# DINx2.net
KiCad netlist of a schematic drawn in EAGLE
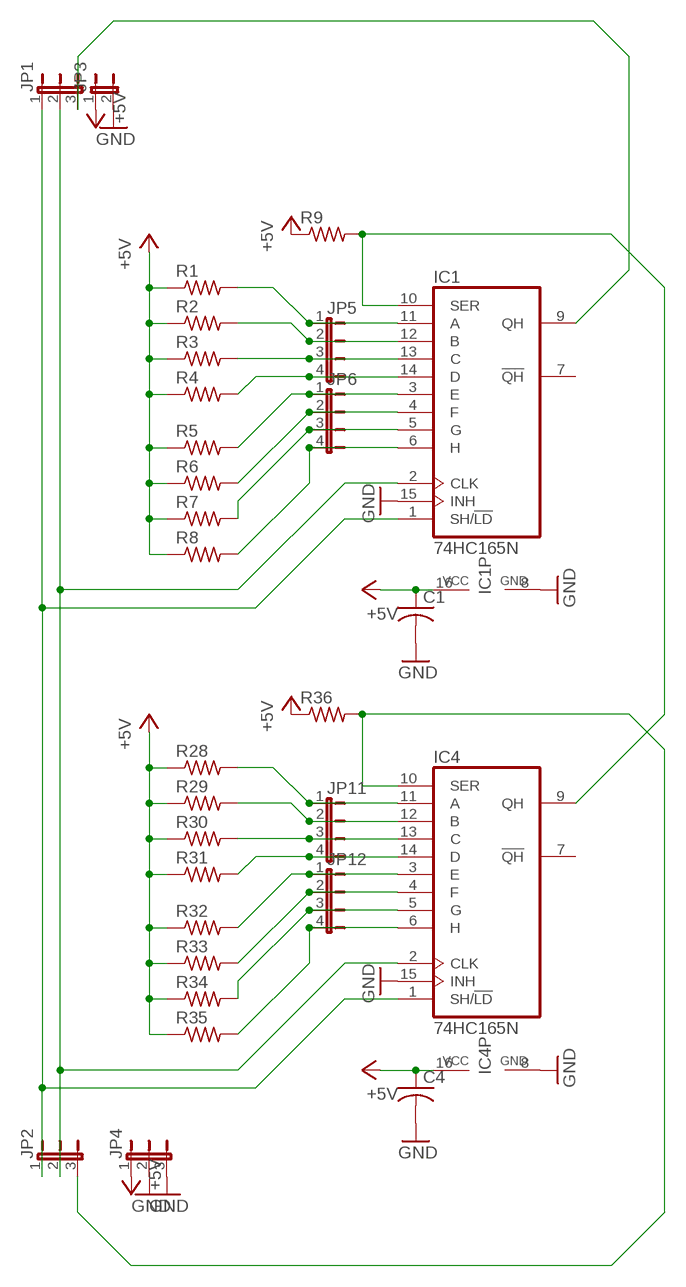
[diagram p0: schematic, sheet 1]

(export (version "E")
  (design (tool "Eeschema 10.0.6"))
  (components
    (comp (ref "C1")
      (value "C-US025-025X050")
      (footprint "eagle-import:C025-025X050")
      (libsource (lib "eagle-import") (part "C-US025-025X050"))
    )
    (comp (ref "C4")
      (value "C-US025-025X050")
      (footprint "eagle-import:C025-025X050")
      (libsource (lib "eagle-import") (part "C-US025-025X050"))
    )
    (comp (ref "IC1")
      (value "74HC165N")
      (footprint "eagle-import:DIL16")
      (libsource (lib "eagle-import") (part "74165NHC"))
    )
    (comp (ref "IC4")
      (value "74HC165N")
      (footprint "eagle-import:DIL16")
      (libsource (lib "eagle-import") (part "74165NHC"))
    )
    (comp (ref "JP1")
      (value "JP2E")
      (footprint "eagle-import:JP2")
      (libsource (lib "eagle-import") (part "JP2E"))
    )
    (comp (ref "JP2")
      (value "JP2E")
      (footprint "eagle-import:JP2")
      (libsource (lib "eagle-import") (part "JP2E"))
    )
    (comp (ref "JP3")
      (value "JP1E")
      (footprint "eagle-import:JP1")
      (libsource (lib "eagle-import") (part "JP1E"))
    )
    (comp (ref "JP4")
      (value "JP2E")
      (footprint "eagle-import:JP2")
      (libsource (lib "eagle-import") (part "JP2E"))
    )
    (comp (ref "JP5")
      (value "JP4E")
      (footprint "eagle-import:JP4")
      (libsource (lib "eagle-import") (part "JP4E"))
    )
    (comp (ref "JP6")
      (value "JP4E")
      (footprint "eagle-import:JP4")
      (libsource (lib "eagle-import") (part "JP4E"))
    )
    (comp (ref "JP11")
      (value "JP4E")
      (footprint "eagle-import:JP4")
      (libsource (lib "eagle-import") (part "JP4E"))
    )
    (comp (ref "JP12")
      (value "JP4E")
      (footprint "eagle-import:JP4")
      (libsource (lib "eagle-import") (part "JP4E"))
    )
    (comp (ref "R1")
      (value "R-US_0207/2V")
      (footprint "eagle-import:0207_2V")
      (libsource (lib "eagle-import") (part "R-US_0207/2V"))
    )
    (comp (ref "R2")
      (value "R-US_0207/2V")
      (footprint "eagle-import:0207_2V")
      (libsource (lib "eagle-import") (part "R-US_0207/2V"))
    )
    (comp (ref "R3")
      (value "R-US_0207/2V")
      (footprint "eagle-import:0207_2V")
      (libsource (lib "eagle-import") (part "R-US_0207/2V"))
    )
    (comp (ref "R4")
      (value "R-US_0207/2V")
      (footprint "eagle-import:0207_2V")
      (libsource (lib "eagle-import") (part "R-US_0207/2V"))
    )
    (comp (ref "R5")
      (value "R-US_0207/2V")
      (footprint "eagle-import:0207_2V")
      (libsource (lib "eagle-import") (part "R-US_0207/2V"))
    )
    (comp (ref "R6")
      (value "R-US_0207/2V")
      (footprint "eagle-import:0207_2V")
      (libsource (lib "eagle-import") (part "R-US_0207/2V"))
    )
    (comp (ref "R7")
      (value "R-US_0207/2V")
      (footprint "eagle-import:0207_2V")
      (libsource (lib "eagle-import") (part "R-US_0207/2V"))
    )
    (comp (ref "R8")
      (value "R-US_0207/2V")
      (footprint "eagle-import:0207_2V")
      (libsource (lib "eagle-import") (part "R-US_0207/2V"))
    )
    (comp (ref "R9")
      (value "R-US_0207/2V")
      (footprint "eagle-import:0207_2V")
      (libsource (lib "eagle-import") (part "R-US_0207/2V"))
    )
    (comp (ref "R28")
      (value "R-US_0207/2V")
      (footprint "eagle-import:0207_2V")
      (libsource (lib "eagle-import") (part "R-US_0207/2V"))
    )
    (comp (ref "R29")
      (value "R-US_0207/2V")
      (footprint "eagle-import:0207_2V")
      (libsource (lib "eagle-import") (part "R-US_0207/2V"))
    )
    (comp (ref "R30")
      (value "R-US_0207/2V")
      (footprint "eagle-import:0207_2V")
      (libsource (lib "eagle-import") (part "R-US_0207/2V"))
    )
    (comp (ref "R31")
      (value "R-US_0207/2V")
      (footprint "eagle-import:0207_2V")
      (libsource (lib "eagle-import") (part "R-US_0207/2V"))
    )
    (comp (ref "R32")
      (value "R-US_0207/2V")
      (footprint "eagle-import:0207_2V")
      (libsource (lib "eagle-import") (part "R-US_0207/2V"))
    )
    (comp (ref "R33")
      (value "R-US_0207/2V")
      (footprint "eagle-import:0207_2V")
      (libsource (lib "eagle-import") (part "R-US_0207/2V"))
    )
    (comp (ref "R34")
      (value "R-US_0207/2V")
      (footprint "eagle-import:0207_2V")
      (libsource (lib "eagle-import") (part "R-US_0207/2V"))
    )
    (comp (ref "R35")
      (value "R-US_0207/2V")
      (footprint "eagle-import:0207_2V")
      (libsource (lib "eagle-import") (part "R-US_0207/2V"))
    )
    (comp (ref "R36")
      (value "R-US_0207/2V")
      (footprint "eagle-import:0207_2V")
      (libsource (lib "eagle-import") (part "R-US_0207/2V"))
    )
  )
  (nets
    (net (code "1") (name "+5V") (class "Default")
      (node (ref "C1") (pin "1") (pinfunction "1_1") (pintype "passive"))
      (node (ref "C4") (pin "1") (pinfunction "1_1") (pintype "passive"))
      (node (ref "IC1") (pin "16") (pinfunction "VCC_16") (pintype "power_in"))
      (node (ref "IC4") (pin "16") (pinfunction "VCC_16") (pintype "power_in"))
      (node (ref "JP3") (pin "1") (pinfunction "1_1") (pintype "passive"))
      (node (ref "JP4") (pin "1") (pinfunction "1_1") (pintype "passive"))
      (node (ref "R1") (pin "1") (pinfunction "1_1") (pintype "passive"))
      (node (ref "R2") (pin "1") (pinfunction "1_1") (pintype "passive"))
      (node (ref "R28") (pin "1") (pinfunction "1_1") (pintype "passive"))
      (node (ref "R29") (pin "1") (pinfunction "1_1") (pintype "passive"))
      (node (ref "R3") (pin "1") (pinfunction "1_1") (pintype "passive"))
      (node (ref "R30") (pin "1") (pinfunction "1_1") (pintype "passive"))
      (node (ref "R31") (pin "1") (pinfunction "1_1") (pintype "passive"))
      (node (ref "R32") (pin "1") (pinfunction "1_1") (pintype "passive"))
      (node (ref "R33") (pin "1") (pinfunction "1_1") (pintype "passive"))
      (node (ref "R34") (pin "1") (pinfunction "1_1") (pintype "passive"))
      (node (ref "R35") (pin "1") (pinfunction "1_1") (pintype "passive"))
      (node (ref "R36") (pin "1") (pinfunction "1_1") (pintype "passive"))
      (node (ref "R4") (pin "1") (pinfunction "1_1") (pintype "passive"))
      (node (ref "R5") (pin "1") (pinfunction "1_1") (pintype "passive"))
      (node (ref "R6") (pin "1") (pinfunction "1_1") (pintype "passive"))
      (node (ref "R7") (pin "1") (pinfunction "1_1") (pintype "passive"))
      (node (ref "R8") (pin "1") (pinfunction "1_1") (pintype "passive"))
      (node (ref "R9") (pin "1") (pinfunction "1_1") (pintype "passive"))
    )
    (net (code "2") (name "GND") (class "Default")
      (node (ref "C1") (pin "2") (pinfunction "2_2") (pintype "passive"))
      (node (ref "C4") (pin "2") (pinfunction "2_2") (pintype "passive"))
      (node (ref "IC1") (pin "15") (pinfunction "INH_15") (pintype "input"))
      (node (ref "IC1") (pin "8") (pinfunction "GND_8") (pintype "power_in"))
      (node (ref "IC4") (pin "15") (pinfunction "INH_15") (pintype "input"))
      (node (ref "IC4") (pin "8") (pinfunction "GND_8") (pintype "power_in"))
      (node (ref "JP3") (pin "2") (pinfunction "2_2") (pintype "passive"))
      (node (ref "JP4") (pin "2") (pinfunction "2_2") (pintype "passive"))
      (node (ref "JP4") (pin "3") (pinfunction "3_3") (pintype "passive"))
    )
    (net (code "3") (name "Net-(IC1A-A)") (class "Default")
      (node (ref "IC1") (pin "11") (pinfunction "A_11") (pintype "input"))
      (node (ref "JP5") (pin "1") (pinfunction "1_1") (pintype "passive"))
      (node (ref "R1") (pin "2") (pinfunction "2_2") (pintype "passive"))
    )
    (net (code "4") (name "Net-(IC1A-B)") (class "Default")
      (node (ref "IC1") (pin "12") (pinfunction "B_12") (pintype "input"))
      (node (ref "JP5") (pin "2") (pinfunction "2_2") (pintype "passive"))
      (node (ref "R2") (pin "2") (pinfunction "2_2") (pintype "passive"))
    )
    (net (code "5") (name "Net-(IC1A-C)") (class "Default")
      (node (ref "IC1") (pin "13") (pinfunction "C_13") (pintype "input"))
      (node (ref "JP5") (pin "3") (pinfunction "3_3") (pintype "passive"))
      (node (ref "R3") (pin "2") (pinfunction "2_2") (pintype "passive"))
    )
    (net (code "6") (name "Net-(IC1A-CLK)") (class "Default")
      (node (ref "IC1") (pin "2") (pinfunction "CLK_2") (pintype "input"))
      (node (ref "IC4") (pin "2") (pinfunction "CLK_2") (pintype "input"))
      (node (ref "JP1") (pin "2") (pinfunction "2_2") (pintype "passive"))
      (node (ref "JP2") (pin "2") (pinfunction "2_2") (pintype "passive"))
    )
    (net (code "7") (name "Net-(IC1A-D)") (class "Default")
      (node (ref "IC1") (pin "14") (pinfunction "D_14") (pintype "input"))
      (node (ref "JP5") (pin "4") (pinfunction "4_4") (pintype "passive"))
      (node (ref "R4") (pin "2") (pinfunction "2_2") (pintype "passive"))
    )
    (net (code "8") (name "Net-(IC1A-E)") (class "Default")
      (node (ref "IC1") (pin "3") (pinfunction "E_3") (pintype "input"))
      (node (ref "JP6") (pin "1") (pinfunction "1_1") (pintype "passive"))
      (node (ref "R5") (pin "2") (pinfunction "2_2") (pintype "passive"))
    )
    (net (code "9") (name "Net-(IC1A-F)") (class "Default")
      (node (ref "IC1") (pin "4") (pinfunction "F_4") (pintype "input"))
      (node (ref "JP6") (pin "2") (pinfunction "2_2") (pintype "passive"))
      (node (ref "R6") (pin "2") (pinfunction "2_2") (pintype "passive"))
    )
    (net (code "10") (name "Net-(IC1A-G)") (class "Default")
      (node (ref "IC1") (pin "5") (pinfunction "G_5") (pintype "input"))
      (node (ref "JP6") (pin "3") (pinfunction "3_3") (pintype "passive"))
      (node (ref "R7") (pin "2") (pinfunction "2_2") (pintype "passive"))
    )
    (net (code "11") (name "Net-(IC1A-H)") (class "Default")
      (node (ref "IC1") (pin "6") (pinfunction "H_6") (pintype "input"))
      (node (ref "JP6") (pin "4") (pinfunction "4_4") (pintype "passive"))
      (node (ref "R8") (pin "2") (pinfunction "2_2") (pintype "passive"))
    )
    (net (code "12") (name "Net-(IC1A-QH)") (class "Default")
      (node (ref "IC1") (pin "9") (pinfunction "QH_9") (pintype "output"))
      (node (ref "JP1") (pin "3") (pinfunction "3_3") (pintype "passive"))
    )
    (net (code "13") (name "Net-(IC1A-SER)") (class "Default")
      (node (ref "IC1") (pin "10") (pinfunction "SER_10") (pintype "input"))
      (node (ref "IC4") (pin "9") (pinfunction "QH_9") (pintype "output"))
      (node (ref "R9") (pin "2") (pinfunction "2_2") (pintype "passive"))
    )
    (net (code "14") (name "Net-(IC1A-SH{slash}~{LD})") (class "Default")
      (node (ref "IC1") (pin "1") (pinfunction "SH/~{LD}_1") (pintype "input"))
      (node (ref "IC4") (pin "1") (pinfunction "SH/~{LD}_1") (pintype "input"))
      (node (ref "JP1") (pin "1") (pinfunction "1_1") (pintype "passive"))
      (node (ref "JP2") (pin "1") (pinfunction "1_1") (pintype "passive"))
    )
    (net (code "15") (name "Net-(IC4A-A)") (class "Default")
      (node (ref "IC4") (pin "11") (pinfunction "A_11") (pintype "input"))
      (node (ref "JP11") (pin "1") (pinfunction "1_1") (pintype "passive"))
      (node (ref "R28") (pin "2") (pinfunction "2_2") (pintype "passive"))
    )
    (net (code "16") (name "Net-(IC4A-B)") (class "Default")
      (node (ref "IC4") (pin "12") (pinfunction "B_12") (pintype "input"))
      (node (ref "JP11") (pin "2") (pinfunction "2_2") (pintype "passive"))
      (node (ref "R29") (pin "2") (pinfunction "2_2") (pintype "passive"))
    )
    (net (code "17") (name "Net-(IC4A-C)") (class "Default")
      (node (ref "IC4") (pin "13") (pinfunction "C_13") (pintype "input"))
      (node (ref "JP11") (pin "3") (pinfunction "3_3") (pintype "passive"))
      (node (ref "R30") (pin "2") (pinfunction "2_2") (pintype "passive"))
    )
    (net (code "18") (name "Net-(IC4A-D)") (class "Default")
      (node (ref "IC4") (pin "14") (pinfunction "D_14") (pintype "input"))
      (node (ref "JP11") (pin "4") (pinfunction "4_4") (pintype "passive"))
      (node (ref "R31") (pin "2") (pinfunction "2_2") (pintype "passive"))
    )
    (net (code "19") (name "Net-(IC4A-E)") (class "Default")
      (node (ref "IC4") (pin "3") (pinfunction "E_3") (pintype "input"))
      (node (ref "JP12") (pin "1") (pinfunction "1_1") (pintype "passive"))
      (node (ref "R32") (pin "2") (pinfunction "2_2") (pintype "passive"))
    )
    (net (code "20") (name "Net-(IC4A-F)") (class "Default")
      (node (ref "IC4") (pin "4") (pinfunction "F_4") (pintype "input"))
      (node (ref "JP12") (pin "2") (pinfunction "2_2") (pintype "passive"))
      (node (ref "R33") (pin "2") (pinfunction "2_2") (pintype "passive"))
    )
    (net (code "21") (name "Net-(IC4A-G)") (class "Default")
      (node (ref "IC4") (pin "5") (pinfunction "G_5") (pintype "input"))
      (node (ref "JP12") (pin "3") (pinfunction "3_3") (pintype "passive"))
      (node (ref "R34") (pin "2") (pinfunction "2_2") (pintype "passive"))
    )
    (net (code "22") (name "Net-(IC4A-H)") (class "Default")
      (node (ref "IC4") (pin "6") (pinfunction "H_6") (pintype "input"))
      (node (ref "JP12") (pin "4") (pinfunction "4_4") (pintype "passive"))
      (node (ref "R35") (pin "2") (pinfunction "2_2") (pintype "passive"))
    )
    (net (code "23") (name "Net-(IC4A-SER)") (class "Default")
      (node (ref "IC4") (pin "10") (pinfunction "SER_10") (pintype "input"))
      (node (ref "JP2") (pin "3") (pinfunction "3_3") (pintype "passive"))
      (node (ref "R36") (pin "2") (pinfunction "2_2") (pintype "passive"))
    )
    (net (code "24") (name "unconnected-(IC1A-~{QH}-Pad7)") (class "Default")
      (node (ref "IC1") (pin "7") (pinfunction "~{QH}_7") (pintype "output"))
    )
    (net (code "25") (name "unconnected-(IC4A-~{QH}-Pad7)") (class "Default")
      (node (ref "IC4") (pin "7") (pinfunction "~{QH}_7") (pintype "output"))
    )
  )
)
